# Fuel_Gauge.net
KiCad netlist of a schematic drawn in Altium Designer
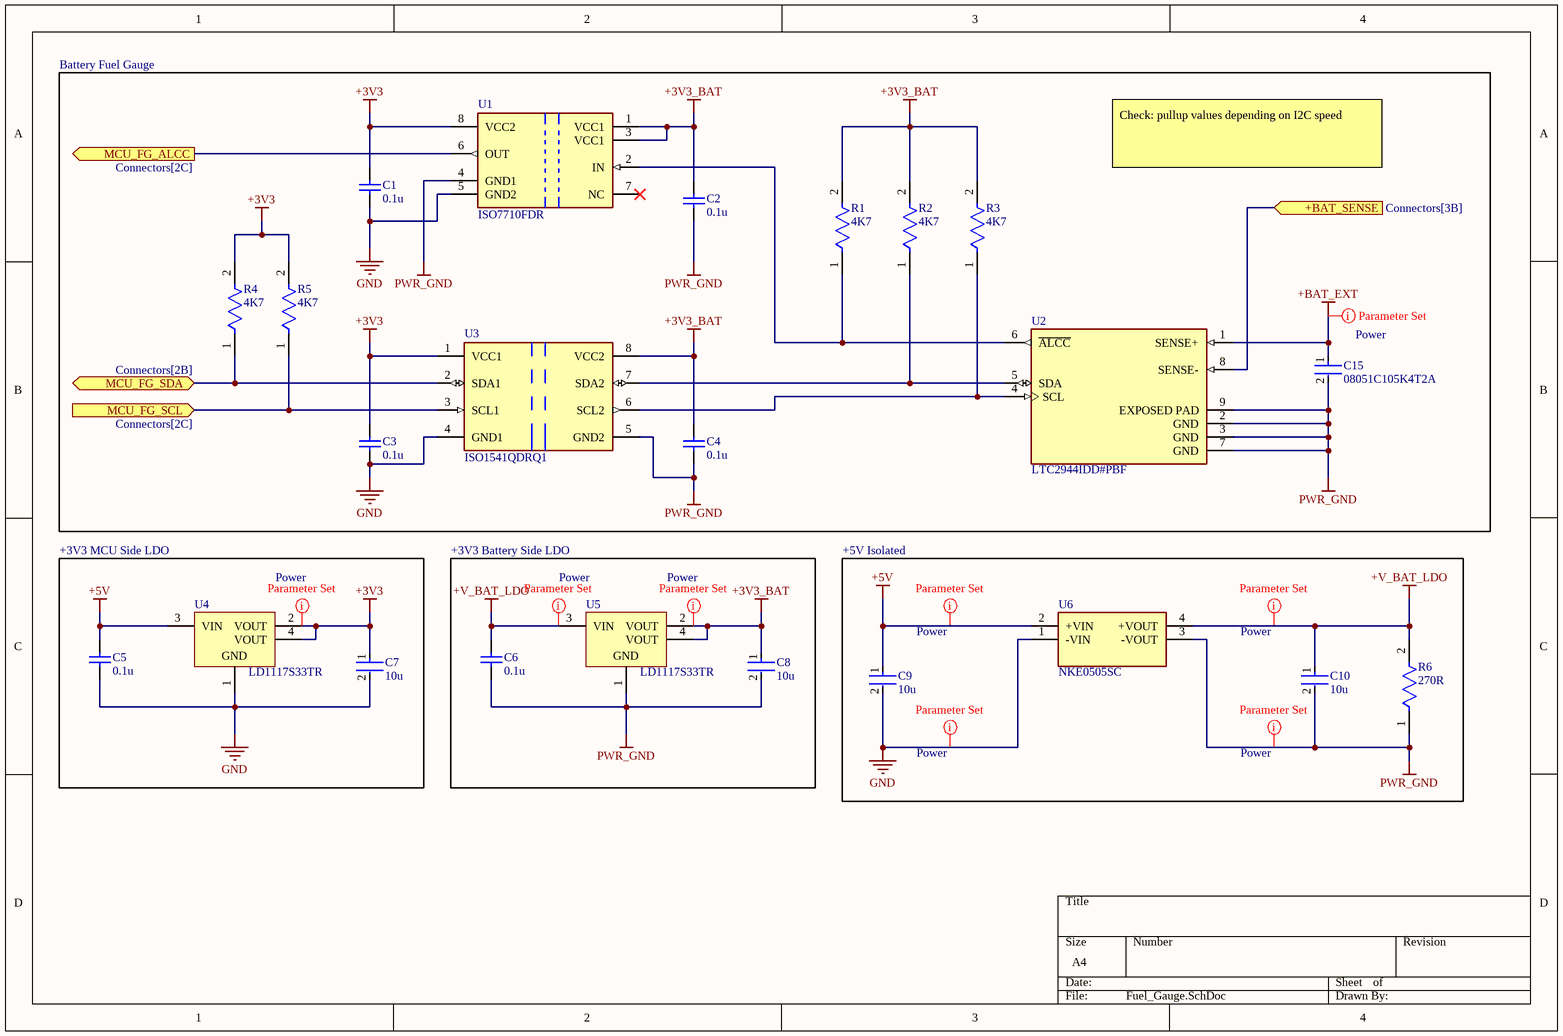
[diagram p0: Fuel_Gauge.SchDoc]

(export (version "E")
  (design (tool "Eeschema 10.0.6"))
  (components
    (comp (ref "C1")
      (value "0.1u")
      (footprint "CAPC2013X145X48NL20T23")
      (fields (field (name "PART NUMBER") "VJ0805Y104KXAMR") (field (name "MANUFACTURER") "Vitramon"))
      (libsource (lib "Altium Content Vault") (part "CAP"))
    )
    (comp (ref "C2")
      (value "0.1u")
      (footprint "CAPC2013X145X48NL20T23")
      (fields (field (name "PART NUMBER") "VJ0805Y104KXAMR") (field (name "MANUFACTURER") "Vitramon"))
      (libsource (lib "Altium Content Vault") (part "CAP"))
    )
    (comp (ref "C3")
      (value "0.1u")
      (footprint "CAPC2013X145X48NL20T23")
      (fields (field (name "PART NUMBER") "VJ0805Y104KXAMR") (field (name "MANUFACTURER") "Vitramon"))
      (libsource (lib "Altium Content Vault") (part "CAP"))
    )
    (comp (ref "C4")
      (value "0.1u")
      (footprint "CAPC2013X145X48NL20T23")
      (fields (field (name "PART NUMBER") "VJ0805Y104KXAMR") (field (name "MANUFACTURER") "Vitramon"))
      (libsource (lib "Altium Content Vault") (part "CAP"))
    )
    (comp (ref "C5")
      (value "0.1u")
      (footprint "CAPC2013X145X48NL20T23")
      (fields (field (name "PART NUMBER") "VJ0805Y104KXAMR") (field (name "MANUFACTURER") "Vitramon"))
      (libsource (lib "Altium Content Vault") (part "CAP"))
    )
    (comp (ref "C6")
      (value "0.1u")
      (footprint "CAPC2013X145X48NL20T23")
      (fields (field (name "PART NUMBER") "VJ0805Y104KXAMR") (field (name "MANUFACTURER") "Vitramon"))
      (libsource (lib "Altium Content Vault") (part "CAP"))
    )
    (comp (ref "C7")
      (value "10u")
      (footprint "FP-CC1206-FD-MFG")
      (description "CAP CER 10UF 50V X5R 1206")
      (fields (field (name "TOLERANCE") "10%"))
      (libsource (lib "Altium Content Vault") (part "b4654b650e69147ec39a6b967a45e02"))
    )
    (comp (ref "C8")
      (value "10u")
      (footprint "FP-CC1206-FD-MFG")
      (description "CAP CER 10UF 50V X5R 1206")
      (fields (field (name "TOLERANCE") "10%"))
      (libsource (lib "Altium Content Vault") (part "b4654b650e69147ec39a6b967a45e02"))
    )
    (comp (ref "C9")
      (value "10u")
      (footprint "FP-CC1206-FD-MFG")
      (description "CAP CER 10UF 50V X5R 1206")
      (fields (field (name "TOLERANCE") "10%"))
      (libsource (lib "Altium Content Vault") (part "b4654b650e69147ec39a6b967a45e02"))
    )
    (comp (ref "C10")
      (value "10u")
      (footprint "FP-CC1206-FD-MFG")
      (description "CAP CER 10UF 50V X5R 1206")
      (fields (field (name "TOLERANCE") "10%"))
      (libsource (lib "Altium Content Vault") (part "b4654b650e69147ec39a6b967a45e02"))
    )
    (comp (ref "C15")
      (value "08051C105K4T2A")
      (footprint "FP-0805-L_2_01_0_2-W_1_25-MFG")
      (description "08051C105K4T2A Cap Ceramic 1uF 100V X7R 10% Pad SMD 0805 125C Automotive T/R")
      (fields (field (name "TOLERANCE") "10%"))
      (libsource (lib "Altium Content Vault") (part "b4654b650e69147ec39a6b967a45e02"))
    )
    (comp (ref "R1")
      (value "4K7")
      (footprint "FP-RT0805-MFG")
      (description "RT0805 4.7KΩ 0.125W 50 ppm/°C 0.01%")
      (fields (field (name "TOLERANCE") "0.0001") (field (name "MANUFACTURER") "Yageo"))
      (libsource (lib "Altium Content Vault") (part "1029c3af85768c4190bb7ad29bc67b5"))
    )
    (comp (ref "R2")
      (value "4K7")
      (footprint "FP-RT0805-MFG")
      (description "RT0805 4.7KΩ 0.125W 50 ppm/°C 0.01%")
      (fields (field (name "TOLERANCE") "0.0001") (field (name "MANUFACTURER") "Yageo"))
      (libsource (lib "Altium Content Vault") (part "1029c3af85768c4190bb7ad29bc67b5"))
    )
    (comp (ref "R3")
      (value "4K7")
      (footprint "FP-RT0805-MFG")
      (description "RT0805 4.7KΩ 0.125W 50 ppm/°C 0.01%")
      (fields (field (name "TOLERANCE") "0.0001") (field (name "MANUFACTURER") "Yageo"))
      (libsource (lib "Altium Content Vault") (part "1029c3af85768c4190bb7ad29bc67b5"))
    )
    (comp (ref "R4")
      (value "4K7")
      (footprint "FP-RT0805-MFG")
      (description "RT0805 4.7KΩ 0.125W 50 ppm/°C 0.01%")
      (fields (field (name "TOLERANCE") "0.0001") (field (name "MANUFACTURER") "Yageo"))
      (libsource (lib "Altium Content Vault") (part "1029c3af85768c4190bb7ad29bc67b5"))
    )
    (comp (ref "R5")
      (value "4K7")
      (footprint "FP-RT0805-MFG")
      (description "RT0805 4.7KΩ 0.125W 50 ppm/°C 0.01%")
      (fields (field (name "TOLERANCE") "0.0001") (field (name "MANUFACTURER") "Yageo"))
      (libsource (lib "Altium Content Vault") (part "1029c3af85768c4190bb7ad29bc67b5"))
    )
    (comp (ref "R6")
      (value "270R")
      (footprint "FP-AF1206-IPC_A")
      (description "Anti-Sulfurated Chip Resistor Automotive Grade 270Ω 5% 0.25W ±100ppm/°C 1206")
      (libsource (lib "Altium Content Vault") (part "1029c3af85768c4190bb7ad29bc67b5"))
    )
    (comp (ref "U1")
      (value "ISO7710FDR")
      (footprint "FP-D0008B-MFG")
      (description "DGTL ISO 3000VRMS 1CH GP 8SOIC")
      (libsource (lib "Altium Content Vault") (part "10e78dd48cadb831ab71e9f14e2447c"))
    )
    (comp (ref "U2")
      (value "LTC2944IDD#PBF")
      (footprint "FP-DD-8-05-08-1698-MFG")
      (description "IC BATTERY GAS GAUGE I2C 8DFN")
      (fields
        (field (name "MANUFACTURER") "Analog Devices")
        (field (name "OCTOPART") "https://octopart.com/ltc2944idd%23pbf-analog+devices-88318751")
      )
      (libsource (lib "Altium Content Vault") (part "2d588ed73019e1f06a7b641f7005350"))
    )
    (comp (ref "U3")
      (value "ISO1541QDRQ1")
      (footprint "FP-D0008A-IPC_B")
      (description "AUTO ISO I2C 2500VRMS 2CH 8SOIC")
      (libsource (lib "Altium Content Vault") (part "109b6026bf777d5de6b5f9bfb67bc76"))
    )
    (comp (ref "U4")
      (value "LD1117S33TR")
      (footprint "SOT-223_L")
      (description "Fixed Low Drop Positive Voltage Regulator, 3.3V, 4-Pin SOT-223, Tape and Reel")
      (libsource (lib "Altium Content Vault") (part "PM-REG-LD1117-SOT4"))
    )
    (comp (ref "U5")
      (value "LD1117S33TR")
      (footprint "SOT-223_L")
      (description "Fixed Low Drop Positive Voltage Regulator, 3.3V, 4-Pin SOT-223, Tape and Reel")
      (libsource (lib "Altium Content Vault") (part "PM-REG-LD1117-SOT4"))
    )
    (comp (ref "U6")
      (value "NKE0505SC")
      (footprint "FP-NKE-SIP-MFG")
      (description "DC DC CONVERTER 12V 1W")
      (fields
        (field (name "OCTOPART") "https://octopart.com/nke1212sc-murata+power+solutions-49448374")
        (field (name "MANUFACTURER") "Murata Power Solutions Inc")
      )
      (libsource (lib "Altium Content Vault") (part "e5226c62c66877018146a6fdffb9fb7"))
    )
  )
  (nets
    (net (code "1") (name "+3V3") (class "Default")
      (node (ref "C1") (pin "2") (pinfunction "2_2") (pintype "passive"))
      (node (ref "C3") (pin "2") (pinfunction "2_2") (pintype "passive"))
      (node (ref "C7") (pin "1") (pinfunction "1_1") (pintype "passive"))
      (node (ref "R4") (pin "2") (pinfunction "2_2") (pintype "passive"))
      (node (ref "R5") (pin "2") (pinfunction "2_2") (pintype "passive"))
      (node (ref "U1") (pin "8") (pinfunction "VCC2_8") (pintype "power_in"))
      (node (ref "U3") (pin "1") (pinfunction "VCC1_1") (pintype "power_in"))
      (node (ref "U4") (pin "2") (pinfunction "VOUT_2") (pintype "power_in"))
      (node (ref "U4") (pin "4") (pinfunction "VOUT_4") (pintype "power_in"))
    )
    (net (code "2") (name "+3V3_BAT") (class "Default")
      (node (ref "C2") (pin "2") (pinfunction "2_2") (pintype "passive"))
      (node (ref "C4") (pin "2") (pinfunction "2_2") (pintype "passive"))
      (node (ref "C8") (pin "1") (pinfunction "1_1") (pintype "passive"))
      (node (ref "R1") (pin "2") (pinfunction "2_2") (pintype "passive"))
      (node (ref "R2") (pin "2") (pinfunction "2_2") (pintype "passive"))
      (node (ref "R3") (pin "2") (pinfunction "2_2") (pintype "passive"))
      (node (ref "U1") (pin "1") (pinfunction "VCC1_1") (pintype "power_in"))
      (node (ref "U1") (pin "3") (pinfunction "VCC1_3") (pintype "power_in"))
      (node (ref "U3") (pin "8") (pinfunction "VCC2_8") (pintype "power_in"))
      (node (ref "U5") (pin "2") (pinfunction "VOUT_2") (pintype "power_in"))
      (node (ref "U5") (pin "4") (pinfunction "VOUT_4") (pintype "power_in"))
    )
    (net (code "3") (name "+5V") (class "Default")
      (node (ref "C5") (pin "2") (pinfunction "2_2") (pintype "passive"))
      (node (ref "C9") (pin "1") (pinfunction "1_1") (pintype "passive"))
      (node (ref "U4") (pin "3") (pinfunction "VIN_3") (pintype "power_in"))
      (node (ref "U6") (pin "2") (pinfunction "+VIN_2") (pintype "power_in"))
    )
    (net (code "4") (name "+BAT_EXT") (class "Default")
      (node (ref "C15") (pin "1") (pinfunction "1_1") (pintype "passive"))
      (node (ref "U2") (pin "1") (pinfunction "SENSE+_1") (pintype "input"))
    )
    (net (code "5") (name "+V_BAT_LDO") (class "Default")
      (node (ref "C10") (pin "1") (pinfunction "1_1") (pintype "passive"))
      (node (ref "C6") (pin "2") (pinfunction "2_2") (pintype "passive"))
      (node (ref "R6") (pin "2") (pinfunction "2_2") (pintype "passive"))
      (node (ref "U5") (pin "3") (pinfunction "VIN_3") (pintype "power_in"))
      (node (ref "U6") (pin "4") (pinfunction "+VOUT_4") (pintype "power_in"))
    )
    (net (code "6") (name "/+BAT_SENSE") (class "Default")
      (node (ref "U2") (pin "8") (pinfunction "SENSE-_8") (pintype "input"))
    )
    (net (code "7") (name "/MCU_FG_ALCC") (class "Default")
      (node (ref "U1") (pin "6") (pinfunction "OUT_6") (pintype "output"))
    )
    (net (code "8") (name "/MCU_FG_SCL") (class "Default")
      (node (ref "R5") (pin "1") (pinfunction "1_1") (pintype "passive"))
      (node (ref "U3") (pin "3") (pinfunction "SCL1_3") (pintype "input"))
    )
    (net (code "9") (name "/MCU_FG_SDA") (class "Default")
      (node (ref "R4") (pin "1") (pinfunction "1_1") (pintype "passive"))
      (node (ref "U3") (pin "2") (pinfunction "SDA1_2") (pintype "bidirectional"))
    )
    (net (code "10") (name "GND") (class "Default")
      (node (ref "C1") (pin "1") (pinfunction "1_1") (pintype "passive"))
      (node (ref "C3") (pin "1") (pinfunction "1_1") (pintype "passive"))
      (node (ref "C5") (pin "1") (pinfunction "1_1") (pintype "passive"))
      (node (ref "C7") (pin "2") (pinfunction "2_2") (pintype "passive"))
      (node (ref "C9") (pin "2") (pinfunction "2_2") (pintype "passive"))
      (node (ref "U1") (pin "5") (pinfunction "GND2_5") (pintype "power_in"))
      (node (ref "U3") (pin "4") (pinfunction "GND1_4") (pintype "power_in"))
      (node (ref "U4") (pin "1") (pinfunction "GND_1") (pintype "power_in"))
      (node (ref "U6") (pin "1") (pinfunction "-VIN_1") (pintype "power_in"))
    )
    (net (code "11") (name "Net-(U1-IN)") (class "Default")
      (node (ref "R1") (pin "1") (pinfunction "1_1") (pintype "passive"))
      (node (ref "U1") (pin "2") (pinfunction "IN_2") (pintype "input"))
      (node (ref "U2") (pin "6") (pinfunction "~{ALCC}_6") (pintype "output"))
    )
    (net (code "12") (name "Net-(U2-SCL)") (class "Default")
      (node (ref "R3") (pin "1") (pinfunction "1_1") (pintype "passive"))
      (node (ref "U2") (pin "4") (pinfunction "SCL_4") (pintype "input"))
      (node (ref "U3") (pin "6") (pinfunction "SCL2_6") (pintype "output"))
    )
    (net (code "13") (name "Net-(U2-SDA)") (class "Default")
      (node (ref "R2") (pin "1") (pinfunction "1_1") (pintype "passive"))
      (node (ref "U2") (pin "5") (pinfunction "SDA_5") (pintype "bidirectional"))
      (node (ref "U3") (pin "7") (pinfunction "SDA2_7") (pintype "bidirectional"))
    )
    (net (code "14") (name "PWR_GND") (class "Default")
      (node (ref "C10") (pin "2") (pinfunction "2_2") (pintype "passive"))
      (node (ref "C15") (pin "2") (pinfunction "2_2") (pintype "passive"))
      (node (ref "C2") (pin "1") (pinfunction "1_1") (pintype "passive"))
      (node (ref "C4") (pin "1") (pinfunction "1_1") (pintype "passive"))
      (node (ref "C6") (pin "1") (pinfunction "1_1") (pintype "passive"))
      (node (ref "C8") (pin "2") (pinfunction "2_2") (pintype "passive"))
      (node (ref "R6") (pin "1") (pinfunction "1_1") (pintype "passive"))
      (node (ref "U1") (pin "4") (pinfunction "GND1_4") (pintype "power_in"))
      (node (ref "U2") (pin "2") (pinfunction "GND_2") (pintype "power_in"))
      (node (ref "U2") (pin "3") (pinfunction "GND_3") (pintype "power_in"))
      (node (ref "U2") (pin "7") (pinfunction "GND_7") (pintype "power_in"))
      (node (ref "U2") (pin "9") (pinfunction "EXPOSED_PAD_9") (pintype "power_in"))
      (node (ref "U3") (pin "5") (pinfunction "GND2_5") (pintype "power_in"))
      (node (ref "U5") (pin "1") (pinfunction "GND_1") (pintype "power_in"))
      (node (ref "U6") (pin "3") (pinfunction "-VOUT_3") (pintype "power_in"))
    )
    (net (code "15") (name "unconnected-(U1-NC-Pad7)") (class "Default")
      (node (ref "U1") (pin "7") (pinfunction "NC_7") (pintype "passive+no_connect"))
    )
  )
)
